# hiiri627v07.net
KiCad netlist of a schematic drawn in Altium Designer
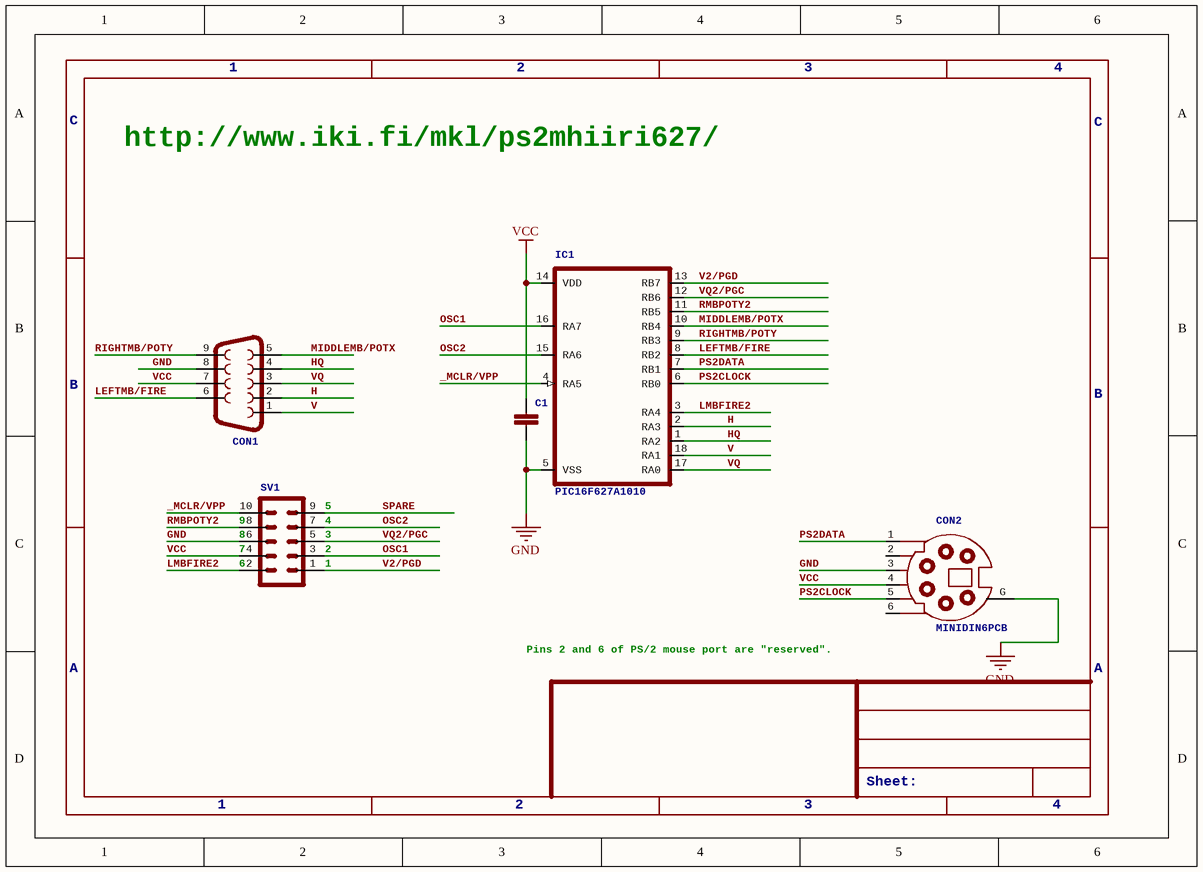
[diagram p0: hiiri627v07.SchDoc]

(export (version "E")
  (design (tool "Eeschema 10.0.6"))
  (components
    (comp (ref "C1")
      (value "C-EUC0805K")
      (footprint "C0805K")
      (description "CAPACITOR, European symbol")
      (libsource (lib "rcl") (part "C-EUC0805K"))
    )
    (comp (ref "CON1")
      (value "F09D")
      (footprint "F09D")
      (description "SUB-D")
      (fields (field (name "LIBRARYNAME") "con-subd"))
      (libsource (lib "con-subd") (part "F09D"))
    )
    (comp (ref "CON2")
      (value "MINIDIN6PCB")
      (footprint "MINIDIN6PCB")
      (fields (field (name "LIBRARYNAME") "0mikacon"))
      (libsource (lib "0mikacon") (part "MINIDIN6PCB"))
    )
    (comp (ref "IC1")
      (value "PIC16F627A1010")
      (footprint "SO18-10101020")
      (fields (field (name "LIBRARYNAME") "0mikalib"))
      (libsource (lib "0mikalib") (part "PIC16F627A1010"))
    )
    (comp (ref "SV1")
      (value "ML10")
      (footprint "ML10")
      (description "HARTING")
      (libsource (lib "con-harting-ml") (part "ML10"))
    )
  )
  (nets
    (net (code "1") (name "/H") (class "Default")
      (node (ref "CON1") (pin "2") (pinfunction "2_2") (pintype "passive"))
      (node (ref "IC1") (pin "2") (pinfunction "RA3_2") (pintype "passive"))
    )
    (net (code "2") (name "/HQ") (class "Default")
      (node (ref "CON1") (pin "4") (pinfunction "4_4") (pintype "passive"))
      (node (ref "IC1") (pin "1") (pinfunction "RA2_1") (pintype "passive"))
    )
    (net (code "3") (name "/LEFTMB{slash}FIRE") (class "Default")
      (node (ref "CON1") (pin "6") (pinfunction "6_6") (pintype "passive"))
      (node (ref "IC1") (pin "8") (pinfunction "RB2_8") (pintype "passive"))
    )
    (net (code "4") (name "/LMBFIRE2") (class "Default")
      (node (ref "IC1") (pin "3") (pinfunction "RA4_3") (pintype "passive"))
      (node (ref "SV1") (pin "2") (pinfunction "2_2") (pintype "passive"))
    )
    (net (code "5") (name "/MIDDLEMB{slash}POTX") (class "Default")
      (node (ref "CON1") (pin "5") (pinfunction "5_5") (pintype "passive"))
      (node (ref "IC1") (pin "10") (pinfunction "RB4_10") (pintype "passive"))
    )
    (net (code "6") (name "/OSC1") (class "Default")
      (node (ref "IC1") (pin "16") (pinfunction "RA7_16") (pintype "passive"))
      (node (ref "SV1") (pin "3") (pinfunction "3_3") (pintype "passive"))
    )
    (net (code "7") (name "/OSC2") (class "Default")
      (node (ref "IC1") (pin "15") (pinfunction "RA6_15") (pintype "passive"))
      (node (ref "SV1") (pin "7") (pinfunction "7_7") (pintype "passive"))
    )
    (net (code "8") (name "/PS2CLOCK") (class "Default")
      (node (ref "CON2") (pin "5") (pinfunction "5_5") (pintype "passive"))
      (node (ref "IC1") (pin "6") (pinfunction "RB0_6") (pintype "passive"))
    )
    (net (code "9") (name "/PS2DATA") (class "Default")
      (node (ref "CON2") (pin "1") (pinfunction "1_1") (pintype "passive"))
      (node (ref "IC1") (pin "7") (pinfunction "RB1_7") (pintype "passive"))
    )
    (net (code "10") (name "/RIGHTMB{slash}POTY") (class "Default")
      (node (ref "CON1") (pin "9") (pinfunction "9_9") (pintype "passive"))
      (node (ref "IC1") (pin "9") (pinfunction "RB3_9") (pintype "passive"))
    )
    (net (code "11") (name "/RMBPOTY2") (class "Default")
      (node (ref "IC1") (pin "11") (pinfunction "RB5_11") (pintype "passive"))
      (node (ref "SV1") (pin "8") (pinfunction "8_8") (pintype "passive"))
    )
    (net (code "12") (name "/SPARE") (class "Default")
      (node (ref "SV1") (pin "9") (pinfunction "9_9") (pintype "passive"))
    )
    (net (code "13") (name "/V") (class "Default")
      (node (ref "CON1") (pin "1") (pinfunction "1_1") (pintype "passive"))
      (node (ref "IC1") (pin "18") (pinfunction "RA1_18") (pintype "passive"))
    )
    (net (code "14") (name "/V2{slash}PGD") (class "Default")
      (node (ref "IC1") (pin "13") (pinfunction "RB7_13") (pintype "passive"))
      (node (ref "SV1") (pin "1") (pinfunction "1_1") (pintype "passive"))
    )
    (net (code "15") (name "/VQ") (class "Default")
      (node (ref "CON1") (pin "3") (pinfunction "3_3") (pintype "passive"))
      (node (ref "IC1") (pin "17") (pinfunction "RA0_17") (pintype "passive"))
    )
    (net (code "16") (name "/VQ2{slash}PGC") (class "Default")
      (node (ref "IC1") (pin "12") (pinfunction "RB6_12") (pintype "passive"))
      (node (ref "SV1") (pin "5") (pinfunction "5_5") (pintype "passive"))
    )
    (net (code "17") (name "/_MCLR{slash}VPP") (class "Default")
      (node (ref "IC1") (pin "4") (pinfunction "RA5_4") (pintype "input"))
      (node (ref "SV1") (pin "10") (pinfunction "10_10") (pintype "passive"))
    )
    (net (code "18") (name "GND") (class "Default")
      (node (ref "C1") (pin "2") (pinfunction "2_2") (pintype "passive"))
      (node (ref "CON1") (pin "8") (pinfunction "8_8") (pintype "passive"))
      (node (ref "CON2") (pin "3") (pinfunction "3_3") (pintype "passive"))
      (node (ref "CON2") (pin "G") (pinfunction "G_G") (pintype "passive"))
      (node (ref "IC1") (pin "5") (pinfunction "VSS_5") (pintype "power_in"))
      (node (ref "SV1") (pin "6") (pinfunction "6_6") (pintype "passive"))
    )
    (net (code "19") (name "VCC") (class "Default")
      (node (ref "C1") (pin "1") (pinfunction "1_1") (pintype "passive"))
      (node (ref "CON1") (pin "7") (pinfunction "7_7") (pintype "passive"))
      (node (ref "CON2") (pin "4") (pinfunction "4_4") (pintype "passive"))
      (node (ref "IC1") (pin "14") (pinfunction "VDD_14") (pintype "power_in"))
      (node (ref "SV1") (pin "4") (pinfunction "4_4") (pintype "passive"))
    )
    (net (code "20") (name "unconnected-(CON2-Pad2)") (class "Default")
      (node (ref "CON2") (pin "2") (pinfunction "2_2") (pintype "passive"))
    )
    (net (code "21") (name "unconnected-(CON2-Pad6)") (class "Default")
      (node (ref "CON2") (pin "6") (pinfunction "6_6") (pintype "passive"))
    )
  )
)
